# ReceiverPCB_trial2.net
KiCad netlist of a schematic drawn in EAGLE
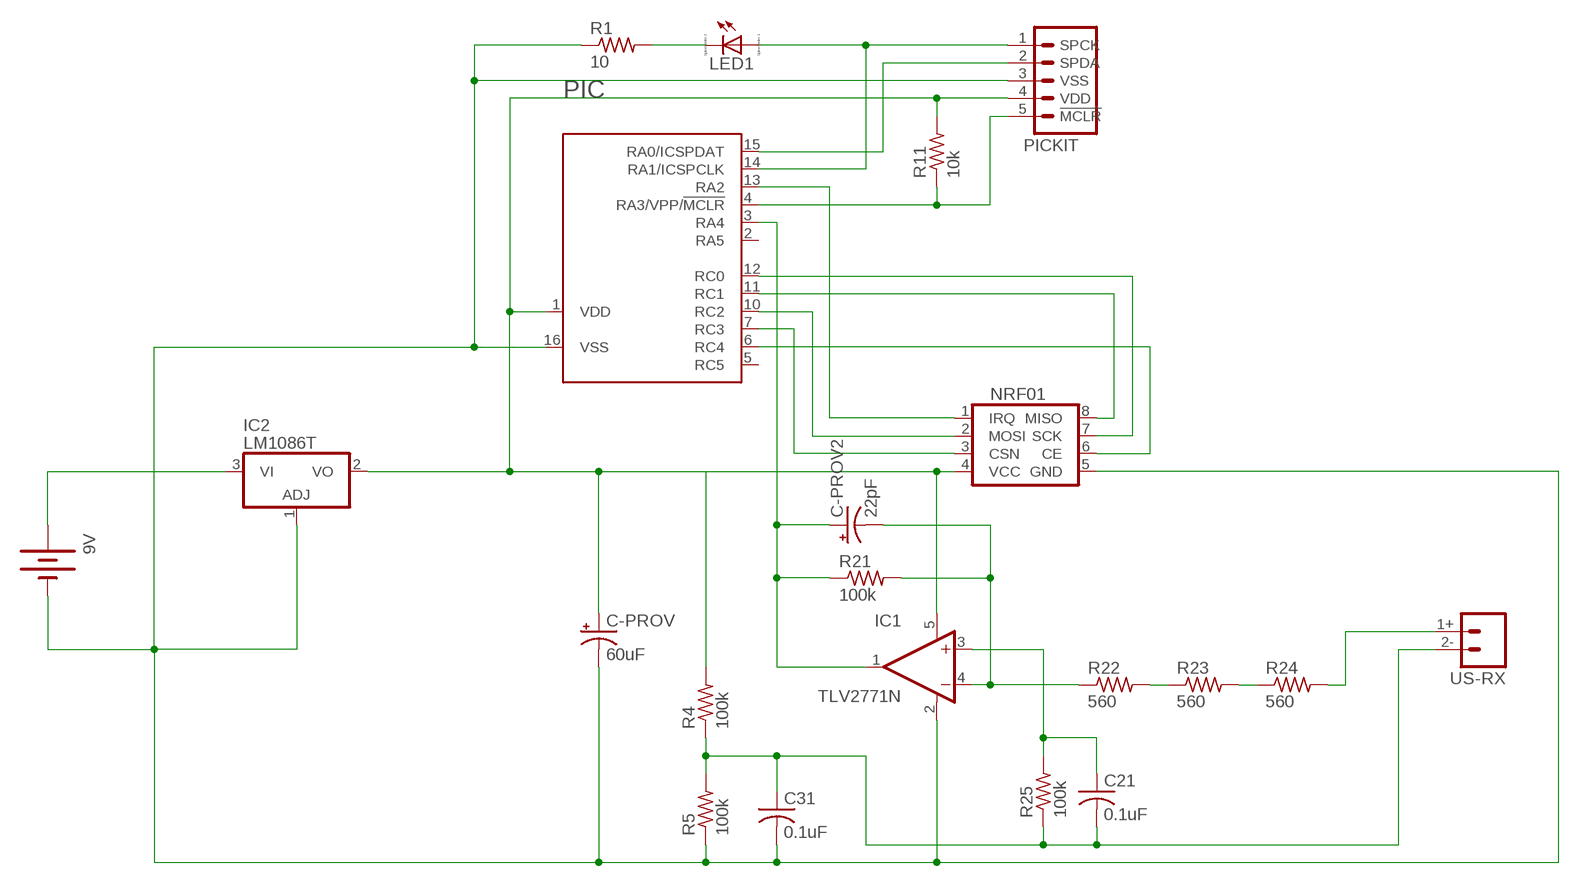
[diagram p0: schematic, sheet 1]

(export (version "E")
  (design (tool "Eeschema 10.0.6"))
  (components
    (comp (ref "9V")
      (value "BATTERY9V")
      (footprint "eagle-import:BATTCON_9V")
      (libsource (lib "eagle-import") (part "BATTERY9V"))
    )
    (comp (ref "C-PROV")
      (value "60uF")
      (footprint "eagle-import:E2,5-6E")
      (libsource (lib "eagle-import") (part "CPOL-USE2,5-6E"))
    )
    (comp (ref "C-PROV2")
      (value "22pF")
      (footprint "eagle-import:E2,5-6E")
      (libsource (lib "eagle-import") (part "CPOL-USE2,5-6E"))
    )
    (comp (ref "C21")
      (value "0.1uF")
      (footprint "eagle-import:C0805")
      (libsource (lib "eagle-import") (part "C-USC0805"))
    )
    (comp (ref "C31")
      (value "0.1uF")
      (footprint "eagle-import:C0805")
      (libsource (lib "eagle-import") (part "C-USC0805"))
    )
    (comp (ref "IC1")
      (value "TLV2771N")
      (footprint "eagle-import:SOT23-5")
      (fields (field (name "MF") "TEXAS INSTRUMENTS") (field (name "MPN") "OPA237NA/250"))
      (libsource (lib "eagle-import") (part "TLV2771N"))
    )
    (comp (ref "IC2")
      (value "LM1086T")
      (footprint "eagle-import:TO220H")
      (libsource (lib "eagle-import") (part "LM1086T"))
    )
    (comp (ref "LED1")
      (value "LED_E")
      (footprint "eagle-import:LED_1206")
      (libsource (lib "eagle-import") (part "LED_E"))
    )
    (comp (ref "NRF01")
      (value "NRF01")
      (footprint "eagle-import:JP4Q")
      (libsource (lib "eagle-import") (part "NRF01"))
    )
    (comp (ref "PIC")
      (value "PIC16F1503(DIL16)")
      (footprint "eagle-import:DIL16")
      (libsource (lib "eagle-import") (part "PIC16F1503(DIL16)"))
    )
    (comp (ref "PICKIT")
      (value "M05PTH")
      (footprint "eagle-import:1X05")
      (libsource (lib "eagle-import") (part "M05PTH"))
    )
    (comp (ref "R1")
      (value "10")
      (footprint "eagle-import:R0805")
      (libsource (lib "eagle-import") (part "R-US_R0805"))
    )
    (comp (ref "R4")
      (value "100k")
      (footprint "eagle-import:R0805")
      (libsource (lib "eagle-import") (part "resistor_348_R-US_R0805"))
    )
    (comp (ref "R5")
      (value "100k")
      (footprint "eagle-import:R0805")
      (libsource (lib "eagle-import") (part "resistor_348_R-US_R0805"))
    )
    (comp (ref "R11")
      (value "10k")
      (footprint "eagle-import:R0805")
      (libsource (lib "eagle-import") (part "resistor_348_R-US_R0805"))
    )
    (comp (ref "R21")
      (value "100k")
      (footprint "eagle-import:R0805")
      (libsource (lib "eagle-import") (part "resistor_348_R-US_R0805"))
    )
    (comp (ref "R22")
      (value "560")
      (footprint "eagle-import:R0805")
      (libsource (lib "eagle-import") (part "resistor_348_R-US_R0805"))
    )
    (comp (ref "R23")
      (value "560")
      (footprint "eagle-import:R0805")
      (libsource (lib "eagle-import") (part "resistor_348_R-US_R0805"))
    )
    (comp (ref "R24")
      (value "560")
      (footprint "eagle-import:R0805")
      (libsource (lib "eagle-import") (part "resistor_348_R-US_R0805"))
    )
    (comp (ref "R25")
      (value "100k")
      (footprint "eagle-import:R0805")
      (libsource (lib "eagle-import") (part "resistor_348_R-US_R0805"))
    )
    (comp (ref "US-RX")
      (value "M02UT-1640K-TT-2-R")
      (footprint "eagle-import:ULTRASONIC-PEIZO")
      (libsource (lib "eagle-import") (part "M02UT-1640K-TT-2-R"))
    )
  )
  (nets
    (net (code "1") (name "Net-(IC1-+IN)") (class "Default")
      (node (ref "C21") (pin "1") (pinfunction "1_1") (pintype "passive"))
      (node (ref "IC1") (pin "3") (pinfunction "+IN_3") (pintype "input"))
      (node (ref "R25") (pin "2") (pinfunction "2_2") (pintype "passive"))
    )
    (net (code "2") (name "Net-(IC1--IN)") (class "Default")
      (node (ref "C-PROV2") (pin "-") (pinfunction "-_-") (pintype "passive"))
      (node (ref "IC1") (pin "4") (pinfunction "-IN_4") (pintype "input"))
      (node (ref "R21") (pin "2") (pinfunction "2_2") (pintype "passive"))
      (node (ref "R22") (pin "1") (pinfunction "1_1") (pintype "passive"))
    )
    (net (code "3") (name "Net-(IC1-OUT)") (class "Default")
      (node (ref "C-PROV2") (pin "+") (pinfunction "+_+") (pintype "passive"))
      (node (ref "IC1") (pin "1") (pinfunction "OUT_1") (pintype "output"))
      (node (ref "PIC") (pin "3") (pinfunction "RA4_3") (pintype "bidirectional"))
      (node (ref "R21") (pin "1") (pinfunction "1_1") (pintype "passive"))
    )
    (net (code "4") (name "Net-(IC1-V+)") (class "Default")
      (node (ref "C-PROV") (pin "+") (pinfunction "+_+") (pintype "passive"))
      (node (ref "IC1") (pin "5") (pinfunction "V+_5") (pintype "power_in"))
      (node (ref "IC2") (pin "2") (pinfunction "VO_2") (pintype "passive"))
      (node (ref "NRF01") (pin "4") (pinfunction "VCC_4") (pintype "passive"))
      (node (ref "PIC") (pin "1") (pinfunction "VDD_1") (pintype "bidirectional"))
      (node (ref "PICKIT") (pin "4") (pinfunction "VDD_4") (pintype "passive"))
      (node (ref "R11") (pin "2") (pinfunction "2_2") (pintype "passive"))
      (node (ref "R4") (pin "2") (pinfunction "2_2") (pintype "passive"))
    )
    (net (code "5") (name "Net-(IC1-V-)") (class "Default")
      (node (ref "9V") (pin "-") (pinfunction "-_-") (pintype "power_in"))
      (node (ref "C-PROV") (pin "-") (pinfunction "-_-") (pintype "passive"))
      (node (ref "C31") (pin "2") (pinfunction "2_2") (pintype "passive"))
      (node (ref "IC1") (pin "2") (pinfunction "V-_2") (pintype "power_in"))
      (node (ref "IC2") (pin "1") (pinfunction "ADJ_1") (pintype "input"))
      (node (ref "NRF01") (pin "5") (pinfunction "GND_5") (pintype "passive"))
      (node (ref "PIC") (pin "16") (pinfunction "VSS_16") (pintype "bidirectional"))
      (node (ref "PICKIT") (pin "3") (pinfunction "VSS_3") (pintype "passive"))
      (node (ref "R1") (pin "1") (pinfunction "1_1") (pintype "passive"))
      (node (ref "R5") (pin "1") (pinfunction "1_1") (pintype "passive"))
    )
    (net (code "6") (name "Net-(IC2-VI)") (class "Default")
      (node (ref "9V") (pin "+") (pinfunction "+_+") (pintype "power_in"))
      (node (ref "IC2") (pin "3") (pinfunction "VI_3") (pintype "input"))
    )
    (net (code "7") (name "Net-(LED1-PadC)") (class "Default")
      (node (ref "LED1") (pin "C") (pinfunction "C_C") (pintype "passive"))
      (node (ref "R1") (pin "2") (pinfunction "2_2") (pintype "passive"))
    )
    (net (code "8") (name "Net-(NRF01-CE)") (class "Default")
      (node (ref "NRF01") (pin "6") (pinfunction "CE_6") (pintype "passive"))
      (node (ref "PIC") (pin "6") (pinfunction "RC4_6") (pintype "bidirectional"))
    )
    (net (code "9") (name "Net-(NRF01-CSN)") (class "Default")
      (node (ref "NRF01") (pin "3") (pinfunction "CSN_3") (pintype "passive"))
      (node (ref "PIC") (pin "7") (pinfunction "RC3_7") (pintype "bidirectional"))
    )
    (net (code "10") (name "Net-(NRF01-IRQ)") (class "Default")
      (node (ref "NRF01") (pin "1") (pinfunction "IRQ_1") (pintype "passive"))
      (node (ref "PIC") (pin "13") (pinfunction "RA2_13") (pintype "bidirectional"))
    )
    (net (code "11") (name "Net-(NRF01-MISO)") (class "Default")
      (node (ref "NRF01") (pin "8") (pinfunction "MISO_8") (pintype "passive"))
      (node (ref "PIC") (pin "11") (pinfunction "RC1_11") (pintype "bidirectional"))
    )
    (net (code "12") (name "Net-(NRF01-MOSI)") (class "Default")
      (node (ref "NRF01") (pin "2") (pinfunction "MOSI_2") (pintype "passive"))
      (node (ref "PIC") (pin "10") (pinfunction "RC2_10") (pintype "bidirectional"))
    )
    (net (code "13") (name "Net-(NRF01-SCK)") (class "Default")
      (node (ref "NRF01") (pin "7") (pinfunction "SCK_7") (pintype "passive"))
      (node (ref "PIC") (pin "12") (pinfunction "RC0_12") (pintype "bidirectional"))
    )
    (net (code "14") (name "Net-(PIC-RA0{slash}ICSPDAT)") (class "Default")
      (node (ref "PIC") (pin "15") (pinfunction "RA0/ICSPDAT_15") (pintype "bidirectional"))
      (node (ref "PICKIT") (pin "2") (pinfunction "SPDA_2") (pintype "passive"))
    )
    (net (code "15") (name "Net-(PIC-RA1{slash}ICSPCLK)") (class "Default")
      (node (ref "LED1") (pin "A") (pinfunction "A_A") (pintype "passive"))
      (node (ref "PIC") (pin "14") (pinfunction "RA1/ICSPCLK_14") (pintype "bidirectional"))
      (node (ref "PICKIT") (pin "1") (pinfunction "SPCK_1") (pintype "passive"))
    )
    (net (code "16") (name "Net-(PIC-RA3{slash}VPP{slash}~{MCLR})") (class "Default")
      (node (ref "PIC") (pin "4") (pinfunction "RA3/VPP/~{MCLR}_4") (pintype "bidirectional"))
      (node (ref "PICKIT") (pin "5") (pinfunction "~{MCLR}_5") (pintype "passive"))
      (node (ref "R11") (pin "1") (pinfunction "1_1") (pintype "passive"))
    )
    (net (code "17") (name "Net-(R22-Pad2)") (class "Default")
      (node (ref "R22") (pin "2") (pinfunction "2_2") (pintype "passive"))
      (node (ref "R23") (pin "1") (pinfunction "1_1") (pintype "passive"))
    )
    (net (code "18") (name "Net-(R23-Pad2)") (class "Default")
      (node (ref "R23") (pin "2") (pinfunction "2_2") (pintype "passive"))
      (node (ref "R24") (pin "1") (pinfunction "1_1") (pintype "passive"))
    )
    (net (code "19") (name "Net-(US-RX-1)") (class "Default")
      (node (ref "R24") (pin "2") (pinfunction "2_2") (pintype "passive"))
      (node (ref "US-RX") (pin "1+") (pinfunction "1_1+") (pintype "passive"))
    )
    (net (code "20") (name "Net-(US-RX-2)") (class "Default")
      (node (ref "C21") (pin "2") (pinfunction "2_2") (pintype "passive"))
      (node (ref "C31") (pin "1") (pinfunction "1_1") (pintype "passive"))
      (node (ref "R25") (pin "1") (pinfunction "1_1") (pintype "passive"))
      (node (ref "R4") (pin "1") (pinfunction "1_1") (pintype "passive"))
      (node (ref "R5") (pin "2") (pinfunction "2_2") (pintype "passive"))
      (node (ref "US-RX") (pin "2-") (pinfunction "2_2-") (pintype "passive"))
    )
    (net (code "21") (name "unconnected-(PIC-RA5-Pad2)") (class "Default")
      (node (ref "PIC") (pin "2") (pinfunction "RA5_2") (pintype "bidirectional"))
    )
    (net (code "22") (name "unconnected-(PIC-RC5-Pad5)") (class "Default")
      (node (ref "PIC") (pin "5") (pinfunction "RC5_5") (pintype "bidirectional"))
    )
  )
)
